# nand2.net
KiCad netlist of a schematic drawn in EAGLE
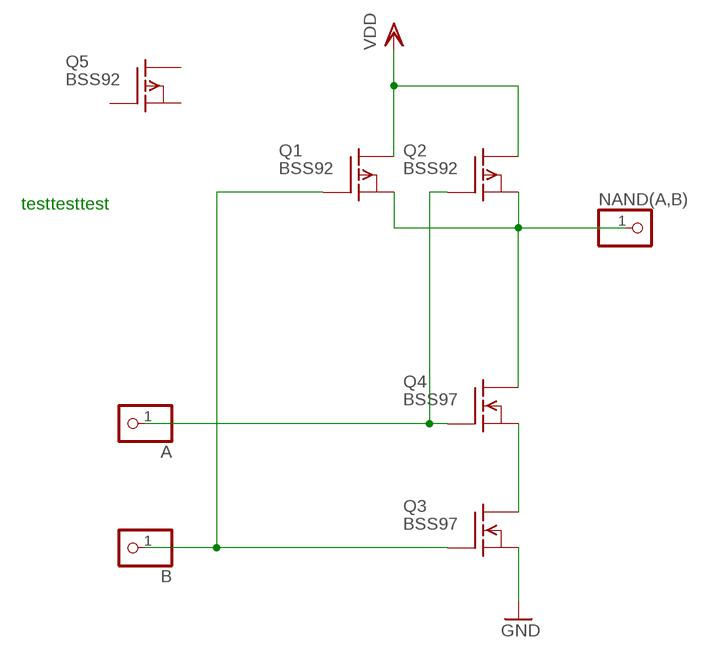
[diagram p0: schematic, sheet 1]

(export (version "E")
  (design (tool "Eeschema 10.0.6"))
  (components
    (comp (ref "A")
      (value "PINHD-1X1")
      (footprint "eagle-import:1X01")
      (libsource (lib "eagle-import") (part "PINHD-1X1"))
    )
    (comp (ref "B")
      (value "PINHD-1X1")
      (footprint "eagle-import:1X01")
      (libsource (lib "eagle-import") (part "PINHD-1X1"))
    )
    (comp (ref "NAND(A,B)")
      (value "PINHD-1X1")
      (footprint "eagle-import:1X01")
      (libsource (lib "eagle-import") (part "PINHD-1X1"))
    )
    (comp (ref "Q1")
      (value "BSS92")
      (footprint "eagle-import:TO92")
      (libsource (lib "eagle-import") (part "BSS92"))
    )
    (comp (ref "Q2")
      (value "BSS92")
      (footprint "eagle-import:TO92")
      (libsource (lib "eagle-import") (part "BSS92"))
    )
    (comp (ref "Q3")
      (value "BSS97")
      (footprint "eagle-import:TO202")
      (libsource (lib "eagle-import") (part "BSS97"))
    )
    (comp (ref "Q4")
      (value "BSS97")
      (footprint "eagle-import:TO202")
      (libsource (lib "eagle-import") (part "BSS97"))
    )
    (comp (ref "Q5")
      (value "BSS92")
      (footprint "eagle-import:TO92")
      (libsource (lib "eagle-import") (part "BSS92"))
    )
  )
  (nets
    (net (code "1") (name "GND") (class "Default")
      (node (ref "Q3") (pin "1") (pinfunction "S_1") (pintype "passive"))
    )
    (net (code "2") (name "Net-(Q1-G)") (class "Default")
      (node (ref "B") (pin "1") (pinfunction "1_1") (pintype "passive"))
      (node (ref "Q1") (pin "1") (pinfunction "G_1") (pintype "passive"))
      (node (ref "Q3") (pin "3") (pinfunction "G_3") (pintype "passive"))
    )
    (net (code "3") (name "Net-(Q1-S)") (class "Default")
      (node (ref "NAND(A,B)") (pin "1") (pinfunction "1_1") (pintype "passive"))
      (node (ref "Q1") (pin "3") (pinfunction "S_3") (pintype "passive"))
      (node (ref "Q2") (pin "3") (pinfunction "S_3") (pintype "passive"))
      (node (ref "Q4") (pin "2") (pinfunction "D_2") (pintype "passive"))
    )
    (net (code "4") (name "Net-(Q2-G)") (class "Default")
      (node (ref "A") (pin "1") (pinfunction "1_1") (pintype "passive"))
      (node (ref "Q2") (pin "1") (pinfunction "G_1") (pintype "passive"))
      (node (ref "Q4") (pin "3") (pinfunction "G_3") (pintype "passive"))
    )
    (net (code "5") (name "Net-(Q3-D)") (class "Default")
      (node (ref "Q3") (pin "2") (pinfunction "D_2") (pintype "passive"))
      (node (ref "Q4") (pin "1") (pinfunction "S_1") (pintype "passive"))
    )
    (net (code "6") (name "VDD") (class "Default")
      (node (ref "Q1") (pin "2") (pinfunction "D_2") (pintype "passive"))
      (node (ref "Q2") (pin "2") (pinfunction "D_2") (pintype "passive"))
    )
    (net (code "7") (name "unconnected-(Q5-D-Pad2)") (class "Default")
      (node (ref "Q5") (pin "2") (pinfunction "D_2") (pintype "passive"))
    )
    (net (code "8") (name "unconnected-(Q5-G-Pad1)") (class "Default")
      (node (ref "Q5") (pin "1") (pinfunction "G_1") (pintype "passive"))
    )
    (net (code "9") (name "unconnected-(Q5-S-Pad3)") (class "Default")
      (node (ref "Q5") (pin "3") (pinfunction "S_3") (pintype "passive"))
    )
  )
)
